# WiFiNode_Pwr_R00.net
KiCad netlist of a schematic drawn in Altium Designer
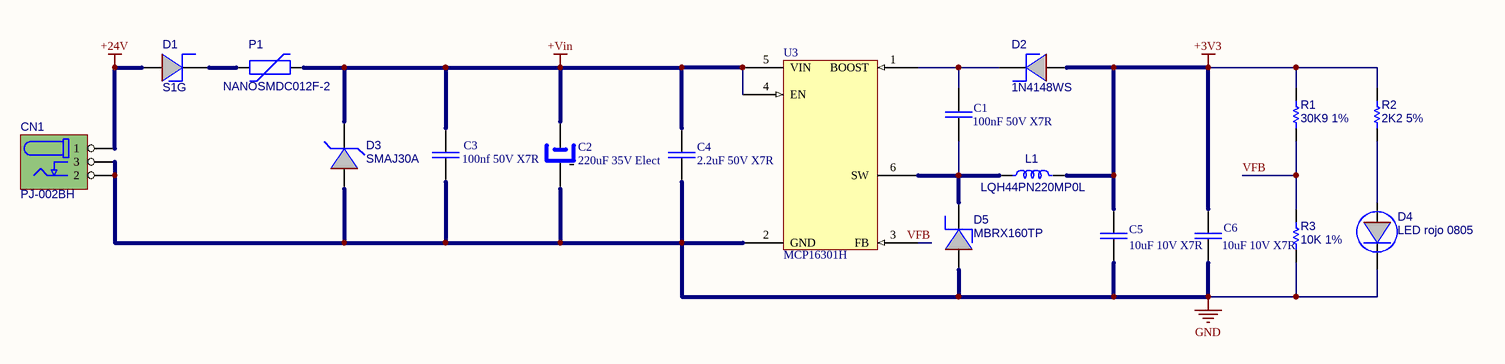
[diagram p0: WiFiNode_Pwr_R00.SchDoc]

(export (version "E")
  (design (tool "Eeschema 10.0.6"))
  (components
    (comp (ref "C1")
      (value "100nF 50V X7R")
      (footprint "C_0805")
      (description "Ceramic Capacitor")
      (libsource (lib "WiFiNode_R00") (part "Ceramic capacitor"))
    )
    (comp (ref "C2")
      (value "220uF 35V Elect")
      (footprint "C_RAD_0.135_H_8X12_S")
      (description "Polarized Capacitor")
      (libsource (lib "WiFiNode_R00") (part "Pol capacitor"))
    )
    (comp (ref "C3")
      (value "100nf 50V X7R")
      (footprint "C_0805")
      (description "Ceramic Capacitor")
      (libsource (lib "WiFiNode_R00") (part "Ceramic capacitor"))
    )
    (comp (ref "C4")
      (value "2.2uF 50V X7R")
      (footprint "C_0805")
      (description "Ceramic Capacitor")
      (libsource (lib "WiFiNode_R00") (part "Ceramic capacitor"))
    )
    (comp (ref "C5")
      (value "10uF 10V X7R")
      (footprint "C_0805")
      (description "Ceramic Capacitor")
      (libsource (lib "WiFiNode_R00") (part "Ceramic capacitor"))
    )
    (comp (ref "C6")
      (value "10uF 10V X7R")
      (footprint "C_0805")
      (description "Ceramic Capacitor")
      (libsource (lib "WiFiNode_R00") (part "Ceramic capacitor"))
    )
    (comp (ref "CN1")
      (value "PJ-002BH")
      (footprint "PJ002B")
      (description "Barrel Power Connector")
      (libsource (lib "WiFiNode_R00") (part "CN_PowerJack"))
    )
    (comp (ref "D1")
      (value "S1G")
      (footprint "D_SMA")
      (description "Diode Shottky")
      (libsource (lib "") (part "DIODO_SH_1"))
    )
    (comp (ref "D2")
      (value "1N4148WS")
      (footprint "SOD_323")
      (description "Diode Shottky")
      (libsource (lib "WiFiNode_R00") (part "DIODO_SH"))
    )
    (comp (ref "D3")
      (value "SMAJ30A")
      (footprint "D_SMA")
      (description "Unidirectional TVS")
      (libsource (lib "WiFiNode_R00") (part "DIODE_TVS"))
    )
    (comp (ref "D4")
      (value "LED rojo 0805")
      (footprint "D_0805")
      (description "LED")
      (libsource (lib "WiFiNode_R00") (part "LED"))
    )
    (comp (ref "D5")
      (value "MBRX160TP")
      (footprint "SOD_123")
      (description "Diode Shottky")
      (libsource (lib "WiFiNode_R00") (part "DIODO_SH"))
    )
    (comp (ref "L1")
      (value "LQH44PN220MP0L")
      (footprint "LQH44")
      (description "Inductor")
      (libsource (lib "WiFiNode_R00") (part "IND"))
    )
    (comp (ref "P1")
      (value "NANOSMDC012F-2")
      (footprint "NANOSMDC")
      (description "Polyswitch")
      (libsource (lib "WiFiNode_R00") (part "PLYSW"))
    )
    (comp (ref "R1")
      (value "30K9 1%")
      (footprint "R_0805")
      (description "Resistor")
      (libsource (lib "WiFiNode_R00") (part "Res1"))
    )
    (comp (ref "R2")
      (value "2K2 5%")
      (footprint "R_0805")
      (description "Resistor")
      (libsource (lib "WiFiNode_R00") (part "Res1"))
    )
    (comp (ref "R3")
      (value "10K 1%")
      (footprint "R_0805")
      (description "Resistor")
      (libsource (lib "WiFiNode_R00") (part "Res1"))
    )
    (comp (ref "U3")
      (value "MCP16301H")
      (footprint "SOT23-6")
      (description "Sted down switching")
      (libsource (lib "WiFiNode_R00") (part "MCP16301"))
    )
  )
  (nets
    (net (code "1") (name "+3V3") (class "Default")
      (node (ref "C5") (pin "1") (pinfunction "1_1") (pintype "passive"))
      (node (ref "C6") (pin "1") (pinfunction "1_1") (pintype "passive"))
      (node (ref "D2") (pin "1") (pinfunction "A_1") (pintype "passive"))
      (node (ref "L1") (pin "2") (pinfunction "2_2") (pintype "passive"))
      (node (ref "R1") (pin "2") (pinfunction "2_2") (pintype "passive"))
      (node (ref "R2") (pin "2") (pinfunction "2_2") (pintype "passive"))
    )
    (net (code "2") (name "+24V") (class "Default")
      (node (ref "CN1") (pin "1") (pinfunction "1_1") (pintype "passive"))
      (node (ref "D1") (pin "1") (pinfunction "A_1") (pintype "passive"))
    )
    (net (code "3") (name "+Vin") (class "Default")
      (node (ref "C2") (pin "1") (pinfunction "1_1") (pintype "passive"))
      (node (ref "C3") (pin "1") (pinfunction "1_1") (pintype "passive"))
      (node (ref "C4") (pin "1") (pinfunction "1_1") (pintype "passive"))
      (node (ref "D3") (pin "2") (pinfunction "K_2") (pintype "passive"))
      (node (ref "P1") (pin "2") (pinfunction "2_2") (pintype "passive"))
      (node (ref "U3") (pin "4") (pinfunction "EN_4") (pintype "input"))
      (node (ref "U3") (pin "5") (pinfunction "VIN_5") (pintype "power_in"))
    )
    (net (code "4") (name "/VFB") (class "Default")
      (node (ref "R1") (pin "1") (pinfunction "1_1") (pintype "passive"))
      (node (ref "R3") (pin "2") (pinfunction "2_2") (pintype "passive"))
      (node (ref "U3") (pin "3") (pinfunction "FB_3") (pintype "input"))
    )
    (net (code "5") (name "GND") (class "Default")
      (node (ref "C2") (pin "2") (pinfunction "2_2") (pintype "passive"))
      (node (ref "C3") (pin "2") (pinfunction "2_2") (pintype "passive"))
      (node (ref "C4") (pin "2") (pinfunction "2_2") (pintype "passive"))
      (node (ref "C5") (pin "2") (pinfunction "2_2") (pintype "passive"))
      (node (ref "C6") (pin "2") (pinfunction "2_2") (pintype "passive"))
      (node (ref "CN1") (pin "2") (pinfunction "2_2") (pintype "passive"))
      (node (ref "CN1") (pin "3") (pinfunction "3_3") (pintype "passive"))
      (node (ref "D3") (pin "1") (pinfunction "A_1") (pintype "passive"))
      (node (ref "D4") (pin "2") (pinfunction "K_2") (pintype "passive"))
      (node (ref "D5") (pin "1") (pinfunction "A_1") (pintype "passive"))
      (node (ref "R3") (pin "1") (pinfunction "1_1") (pintype "passive"))
      (node (ref "U3") (pin "2") (pinfunction "GND_2") (pintype "power_in"))
    )
    (net (code "6") (name "Net-(D1-K)") (class "Default")
      (node (ref "D1") (pin "2") (pinfunction "K_2") (pintype "passive"))
      (node (ref "P1") (pin "1") (pinfunction "1_1") (pintype "passive"))
    )
    (net (code "7") (name "Net-(D2-K)") (class "Default")
      (node (ref "C1") (pin "1") (pinfunction "1_1") (pintype "passive"))
      (node (ref "D2") (pin "2") (pinfunction "K_2") (pintype "passive"))
      (node (ref "U3") (pin "1") (pinfunction "BOOST_1") (pintype "input"))
    )
    (net (code "8") (name "Net-(D4-A)") (class "Default")
      (node (ref "D4") (pin "1") (pinfunction "A_1") (pintype "passive"))
      (node (ref "R2") (pin "1") (pinfunction "1_1") (pintype "passive"))
    )
    (net (code "9") (name "Net-(D5-K)") (class "Default")
      (node (ref "C1") (pin "2") (pinfunction "2_2") (pintype "passive"))
      (node (ref "D5") (pin "2") (pinfunction "K_2") (pintype "passive"))
      (node (ref "L1") (pin "1") (pinfunction "1_1") (pintype "passive"))
      (node (ref "U3") (pin "6") (pinfunction "SW_6") (pintype "power_in"))
    )
  )
)
